# WatchDogAlarm_rev1_3.net
KiCad netlist of a schematic drawn in Altium Designer
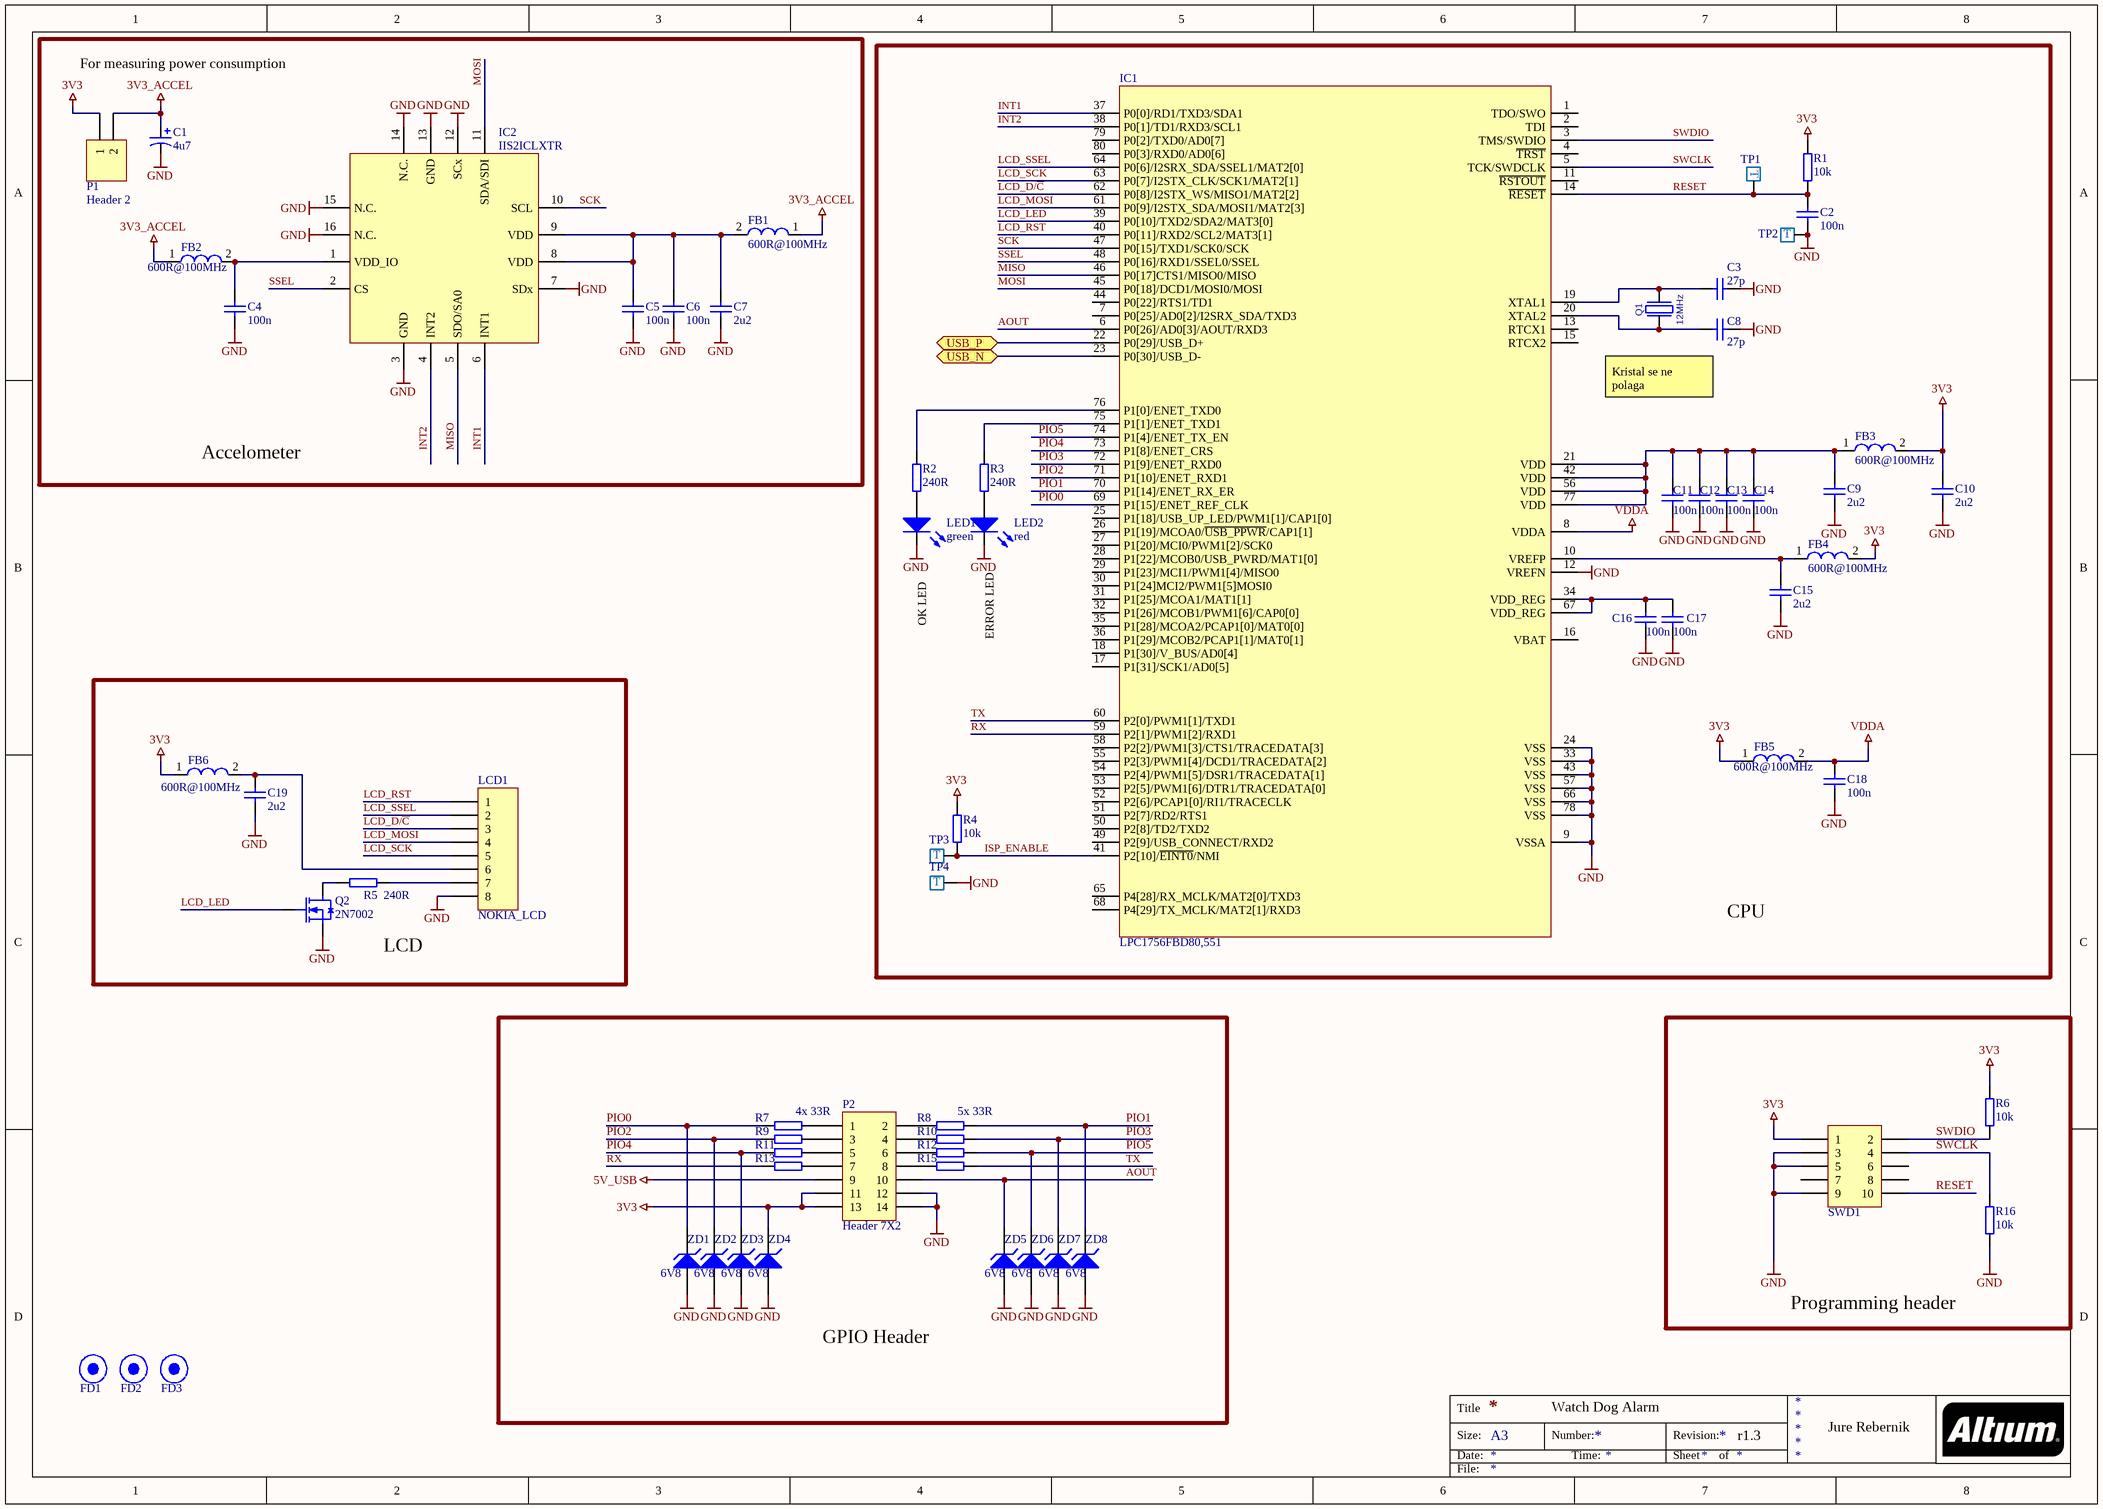
[diagram p0: WatchDogAlarm_rev1_3.SchDoc]

(export (version "E")
  (design (tool "Eeschema 10.0.6"))
  (components
    (comp (ref "C1")
      (value "4u7")
      (footprint "Tantalum 3216")
      (description "Generic polarized capacitor")
      (libsource (lib "WatchDogAlarm_rev1_3") (part "Capacitor - polarized"))
    )
    (comp (ref "C2")
      (value "100n")
      (footprint "SMD_C0603")
      (description "Capacitor")
      (libsource (lib "WatchDogAlarm_rev1_3") (part "CAP"))
    )
    (comp (ref "C3")
      (value "27p")
      (footprint "SMD_C0603")
      (description "Capacitor")
      (libsource (lib "WatchDogAlarm_rev1_3") (part "CAP"))
    )
    (comp (ref "C4")
      (value "100n")
      (footprint "SMD_C0603")
      (description "Capacitor")
      (libsource (lib "WatchDogAlarm_rev1_3") (part "CAP"))
    )
    (comp (ref "C5")
      (value "100n")
      (footprint "SMD_C0603")
      (description "Capacitor")
      (libsource (lib "WatchDogAlarm_rev1_3") (part "CAP"))
    )
    (comp (ref "C6")
      (value "100n")
      (footprint "SMD_C0603")
      (description "Capacitor")
      (libsource (lib "WatchDogAlarm_rev1_3") (part "CAP"))
    )
    (comp (ref "C7")
      (value "2u2")
      (footprint "SMD_C0805")
      (description "Capacitor")
      (libsource (lib "WatchDogAlarm_rev1_3") (part "CAP"))
    )
    (comp (ref "C8")
      (value "27p")
      (footprint "SMD_C0603")
      (description "Capacitor")
      (libsource (lib "WatchDogAlarm_rev1_3") (part "CAP"))
    )
    (comp (ref "C9")
      (value "2u2")
      (footprint "SMD_C0805")
      (description "Capacitor")
      (libsource (lib "WatchDogAlarm_rev1_3") (part "CAP"))
    )
    (comp (ref "C10")
      (value "2u2")
      (footprint "SMD_C0805")
      (description "Capacitor")
      (libsource (lib "WatchDogAlarm_rev1_3") (part "CAP"))
    )
    (comp (ref "C11")
      (value "100n")
      (footprint "SMD_C0603")
      (description "Capacitor")
      (libsource (lib "WatchDogAlarm_rev1_3") (part "CAP"))
    )
    (comp (ref "C12")
      (value "100n")
      (footprint "SMD_C0603")
      (description "Capacitor")
      (libsource (lib "WatchDogAlarm_rev1_3") (part "CAP"))
    )
    (comp (ref "C13")
      (value "100n")
      (footprint "SMD_C0603")
      (description "Capacitor")
      (libsource (lib "WatchDogAlarm_rev1_3") (part "CAP"))
    )
    (comp (ref "C14")
      (value "100n")
      (footprint "SMD_C0603")
      (description "Capacitor")
      (libsource (lib "WatchDogAlarm_rev1_3") (part "CAP"))
    )
    (comp (ref "C15")
      (value "2u2")
      (footprint "SMD_C0805")
      (description "Capacitor")
      (libsource (lib "WatchDogAlarm_rev1_3") (part "CAP"))
    )
    (comp (ref "C16")
      (value "100n")
      (footprint "SMD_C0603")
      (description "Capacitor")
      (libsource (lib "WatchDogAlarm_rev1_3") (part "CAP"))
    )
    (comp (ref "C17")
      (value "100n")
      (footprint "SMD_C0603")
      (description "Capacitor")
      (libsource (lib "WatchDogAlarm_rev1_3") (part "CAP"))
    )
    (comp (ref "C18")
      (value "100n")
      (footprint "SMD_C0603")
      (description "Capacitor")
      (libsource (lib "WatchDogAlarm_rev1_3") (part "CAP"))
    )
    (comp (ref "C19")
      (value "2u2")
      (footprint "SMD_C0805")
      (description "Capacitor")
      (libsource (lib "WatchDogAlarm_rev1_3") (part "CAP"))
    )
    (comp (ref "FB1")
      (value "600R@100MHz")
      (footprint "SMD_R0603")
      (description "Ferrite bead")
      (libsource (lib "") (part "FB_1"))
    )
    (comp (ref "FB2")
      (value "600R@100MHz")
      (footprint "SMD_R0603")
      (description "Ferrite bead")
      (libsource (lib "WatchDogAlarm_rev1_3") (part "FB"))
    )
    (comp (ref "FB3")
      (value "600R@100MHz")
      (footprint "SMD_R0603")
      (description "Ferrite bead")
      (libsource (lib "WatchDogAlarm_rev1_3") (part "FB"))
    )
    (comp (ref "FB4")
      (value "600R@100MHz")
      (footprint "SMD_R0603")
      (description "Ferrite bead")
      (libsource (lib "WatchDogAlarm_rev1_3") (part "FB"))
    )
    (comp (ref "FB5")
      (value "600R@100MHz")
      (footprint "SMD_R0603")
      (description "Ferrite bead")
      (libsource (lib "WatchDogAlarm_rev1_3") (part "FB"))
    )
    (comp (ref "FB6")
      (value "600R@100MHz")
      (footprint "SMD_R0603")
      (description "Ferrite bead")
      (libsource (lib "WatchDogAlarm_rev1_3") (part "FB"))
    )
    (comp (ref "FD1")
      (value "Fiducial 1mm")
      (footprint "FID1")
      (libsource (lib "WatchDogAlarm_rev1_3") (part "FIDUCIAL"))
    )
    (comp (ref "FD2")
      (value "Fiducial 1mm")
      (footprint "FID1")
      (libsource (lib "WatchDogAlarm_rev1_3") (part "FIDUCIAL"))
    )
    (comp (ref "FD3")
      (value "Fiducial 1mm")
      (footprint "FID1")
      (libsource (lib "WatchDogAlarm_rev1_3") (part "FIDUCIAL"))
    )
    (comp (ref "IC1")
      (value "LPC1756FBD80,551")
      (footprint "LQFP80")
      (description "LPC1756FBD80")
      (fields (field (name "MANUFACTURER") "NXP"))
      (libsource (lib "WatchDogAlarm_rev1_3") (part "LPC1756FBD80"))
    )
    (comp (ref "IC2")
      (value "IIS2ICLXTR")
      (footprint "LGA-16L")
      (fields (field (name "MANUFACTURER") "STM"))
      (libsource (lib "WatchDogAlarm_SchLib") (part "IIS2ICLXTR"))
    )
    (comp (ref "LCD1")
      (value "NOKIA_LCD")
      (footprint "NOKIA_LCD")
      (libsource (lib "WatchDogAlarm_rev1_3") (part "NOKIA_LCD"))
    )
    (comp (ref "LED1") (value "green") (footprint "SMD_LD0603") (libsource (lib "Atlan") (part "LED")))
    (comp (ref "LED2") (value "red") (footprint "SMD_LD0603") (libsource (lib "Atlan") (part "LED")))
    (comp (ref "P1")
      (value "Header 2")
      (footprint "HDR1X2")
      (description "Header, 2-Pin")
      (fields (field (name "PUBLISHER") "Altium Limited"))
      (libsource (lib "Miscellaneous Connectors") (part "Header 2"))
    )
    (comp (ref "P2")
      (value "Header 7X2")
      (footprint "HDR2X7")
      (description "Header, 7-Pin, Dual row")
      (fields (field (name "PUBLISHER") "Altium Limited"))
      (libsource (lib "WatchDogAlarm_rev1_3") (part "Header 7X2"))
    )
    (comp (ref "Q1")
      (value "12MHz")
      (footprint "QABM3")
      (description "Crystal")
      (fields (field (name "PARTNUMBER") "ABM3-12.000MHZ-D2Y-T") (field (name "MANUFACTURER") "ABRACON"))
      (libsource (lib "WatchDogAlarm_rev1_3") (part "Crystal"))
    )
    (comp (ref "Q2")
      (value "2N7002")
      (footprint "SOT-23")
      (description "Power MOSFET, N Channel, 60 V, 300 mA, 2.8 ohm, SOT-23, Surface Mount")
      (fields (field (name "MANUFACTURER") "NXP"))
      (libsource (lib "WatchDogAlarm_rev1_3") (part "N-MOSFET"))
    )
    (comp (ref "R1")
      (value "10k")
      (footprint "SMD_R0603")
      (libsource (lib "WatchDogAlarm_rev1_3") (part "RESISTOR"))
    )
    (comp (ref "R2")
      (value "240R")
      (footprint "SMD_R0603")
      (libsource (lib "WatchDogAlarm_rev1_3") (part "RESISTOR"))
    )
    (comp (ref "R3")
      (value "240R")
      (footprint "SMD_R0603")
      (libsource (lib "WatchDogAlarm_rev1_3") (part "RESISTOR"))
    )
    (comp (ref "R4")
      (value "10k")
      (footprint "SMD_R0603")
      (libsource (lib "WatchDogAlarm_rev1_3") (part "RESISTOR"))
    )
    (comp (ref "R5")
      (value "240R")
      (footprint "SMD_R0603")
      (libsource (lib "WatchDogAlarm_rev1_3") (part "RESISTOR"))
    )
    (comp (ref "R6")
      (value "10k")
      (footprint "SMD_R0603")
      (libsource (lib "WatchDogAlarm_rev1_3") (part "RESISTOR"))
    )
    (comp (ref "R7")
      (value "33R")
      (footprint "SMD_R0603")
      (libsource (lib "WatchDogAlarm_rev1_3") (part "RESISTOR"))
    )
    (comp (ref "R8")
      (value "33R")
      (footprint "SMD_R0603")
      (libsource (lib "WatchDogAlarm_rev1_3") (part "RESISTOR"))
    )
    (comp (ref "R9")
      (value "33R")
      (footprint "SMD_R0603")
      (libsource (lib "WatchDogAlarm_rev1_3") (part "RESISTOR"))
    )
    (comp (ref "R10")
      (value "33R")
      (footprint "SMD_R0603")
      (libsource (lib "WatchDogAlarm_rev1_3") (part "RESISTOR"))
    )
    (comp (ref "R11")
      (value "33R")
      (footprint "SMD_R0603")
      (libsource (lib "WatchDogAlarm_rev1_3") (part "RESISTOR"))
    )
    (comp (ref "R12")
      (value "33R")
      (footprint "SMD_R0603")
      (libsource (lib "WatchDogAlarm_rev1_3") (part "RESISTOR"))
    )
    (comp (ref "R13")
      (value "33R")
      (footprint "SMD_R0603")
      (libsource (lib "WatchDogAlarm_rev1_3") (part "RESISTOR"))
    )
    (comp (ref "R15")
      (value "33R")
      (footprint "SMD_R0603")
      (libsource (lib "WatchDogAlarm_rev1_3") (part "RESISTOR"))
    )
    (comp (ref "R16")
      (value "10k")
      (footprint "SMD_R0603")
      (libsource (lib "WatchDogAlarm_rev1_3") (part "RESISTOR"))
    )
    (comp (ref "SWD1")
      (value "Header 5x2")
      (footprint "2x5_SWD_CON")
      (description "Header, 5-Pin, Dual row")
      (fields (field (name "MANUFACTURER") "HARWIN") (field (name "PARTNUMBER") "M50-3500542"))
      (libsource (lib "WatchDogAlarm_rev1_3") (part "Header 5X2"))
    )
    (comp (ref "TP1")
      (value "TEST_PAD_1.5mm")
      (footprint "TEST_PAD_1.5mm")
      (libsource (lib "Atlan") (part "TEST_PAD"))
    )
    (comp (ref "TP2")
      (value "TEST_PAD_1.5mm")
      (footprint "TEST_PAD_1.5mm")
      (libsource (lib "Atlan") (part "TEST_PAD"))
    )
    (comp (ref "TP3")
      (value "TEST_PAD_1.5mm")
      (footprint "TEST_PAD_1.5mm")
      (libsource (lib "Atlan") (part "TEST_PAD"))
    )
    (comp (ref "TP4")
      (value "TEST_PAD_1.5mm")
      (footprint "TEST_PAD_1.5mm")
      (libsource (lib "Atlan") (part "TEST_PAD"))
    )
    (comp (ref "ZD1")
      (value "6V8")
      (footprint "SOT-23")
      (description "Zener Diode")
      (fields (field (name "MANUFACTURER") "ON Semiconductor") (field (name "PARTNUMBER") "BZX84C6V8LT1G"))
      (libsource (lib "WatchDogAlarm_rev1_3") (part "ZenerDiode"))
    )
    (comp (ref "ZD2")
      (value "6V8")
      (footprint "SOT-23")
      (description "Zener Diode")
      (fields (field (name "MANUFACTURER") "ON Semiconductor") (field (name "PARTNUMBER") "BZX84C6V8LT1G"))
      (libsource (lib "WatchDogAlarm_rev1_3") (part "ZenerDiode"))
    )
    (comp (ref "ZD3")
      (value "6V8")
      (footprint "SOT-23")
      (description "Zener Diode")
      (fields (field (name "MANUFACTURER") "ON Semiconductor") (field (name "PARTNUMBER") "BZX84C6V8LT1G"))
      (libsource (lib "WatchDogAlarm_rev1_3") (part "ZenerDiode"))
    )
    (comp (ref "ZD4")
      (value "6V8")
      (footprint "SOT-23")
      (description "Zener Diode")
      (fields (field (name "MANUFACTURER") "ON Semiconductor") (field (name "PARTNUMBER") "BZX84C6V8LT1G"))
      (libsource (lib "WatchDogAlarm_rev1_3") (part "ZenerDiode"))
    )
    (comp (ref "ZD5")
      (value "6V8")
      (footprint "SOT-23")
      (description "Zener Diode")
      (fields (field (name "MANUFACTURER") "ON Semiconductor") (field (name "PARTNUMBER") "BZX84C6V8LT1G"))
      (libsource (lib "WatchDogAlarm_rev1_3") (part "ZenerDiode"))
    )
    (comp (ref "ZD6")
      (value "6V8")
      (footprint "SOT-23")
      (description "Zener Diode")
      (fields (field (name "MANUFACTURER") "ON Semiconductor") (field (name "PARTNUMBER") "BZX84C6V8LT1G"))
      (libsource (lib "WatchDogAlarm_rev1_3") (part "ZenerDiode"))
    )
    (comp (ref "ZD7")
      (value "6V8")
      (footprint "SOT-23")
      (description "Zener Diode")
      (fields (field (name "MANUFACTURER") "ON Semiconductor") (field (name "PARTNUMBER") "BZX84C6V8LT1G"))
      (libsource (lib "WatchDogAlarm_rev1_3") (part "ZenerDiode"))
    )
    (comp (ref "ZD8")
      (value "6V8")
      (footprint "SOT-23")
      (description "Zener Diode")
      (fields (field (name "MANUFACTURER") "ON Semiconductor") (field (name "PARTNUMBER") "BZX84C6V8LT1G"))
      (libsource (lib "WatchDogAlarm_rev1_3") (part "ZenerDiode"))
    )
  )
  (nets
    (net (code "1") (name "/AOUT") (class "Default")
      (node (ref "IC1") (pin "6") (pinfunction "P0[26]/AD0[3]/AOUT/RXD3_6") (pintype "passive"))
      (node (ref "P2") (pin "10") (pinfunction "10_10") (pintype "passive"))
      (node (ref "ZD5") (pin "3") (pinfunction "K_3") (pintype "passive"))
    )
    (net (code "2") (name "/INT1") (class "Default")
      (node (ref "IC1") (pin "37") (pinfunction "P0[0]/RD1/TXD3/SDA1_37") (pintype "passive"))
      (node (ref "IC2") (pin "6") (pinfunction "INT1_6") (pintype "passive"))
    )
    (net (code "3") (name "/INT2") (class "Default")
      (node (ref "IC1") (pin "38") (pinfunction "P0[1]/TD1/RXD3/SCL1_38") (pintype "passive"))
      (node (ref "IC2") (pin "4") (pinfunction "INT2_4") (pintype "passive"))
    )
    (net (code "4") (name "/ISP_ENABLE") (class "Default")
      (node (ref "IC1") (pin "41") (pinfunction "P2[10]/~{EINT0}/NMI_41") (pintype "passive"))
      (node (ref "R4") (pin "1") (pintype "passive"))
      (node (ref "TP3") (pin "1") (pintype "passive"))
    )
    (net (code "5") (name "/LCD_D{slash}~{C}") (class "Default")
      (node (ref "IC1") (pin "62") (pinfunction "P0[8]/I2STX_WS/MISO1/MAT2[2]_62") (pintype "passive"))
      (node (ref "LCD1") (pin "3") (pinfunction "3_3") (pintype "passive"))
    )
    (net (code "6") (name "/LCD_LED") (class "Default")
      (node (ref "IC1") (pin "39") (pinfunction "P0[10]/TXD2/SDA2/MAT3[0]_39") (pintype "passive"))
      (node (ref "Q2") (pin "1") (pinfunction "G_1") (pintype "passive"))
    )
    (net (code "7") (name "/LCD_MOSI") (class "Default")
      (node (ref "IC1") (pin "61") (pinfunction "P0[9]/I2STX_SDA/MOSI1/MAT2[3]_61") (pintype "passive"))
      (node (ref "LCD1") (pin "4") (pinfunction "4_4") (pintype "passive"))
    )
    (net (code "8") (name "/LCD_RST") (class "Default")
      (node (ref "IC1") (pin "40") (pinfunction "P0[11]/RXD2/SCL2/MAT3[1]_40") (pintype "passive"))
      (node (ref "LCD1") (pin "1") (pinfunction "1_1") (pintype "passive"))
    )
    (net (code "9") (name "/LCD_SCK") (class "Default")
      (node (ref "IC1") (pin "63") (pinfunction "P0[7]/I2STX_CLK/SCK1/MAT2[1]_63") (pintype "passive"))
      (node (ref "LCD1") (pin "5") (pinfunction "5_5") (pintype "passive"))
    )
    (net (code "10") (name "/LCD_SSEL") (class "Default")
      (node (ref "IC1") (pin "64") (pinfunction "P0[6]/I2SRX_SDA/SSEL1/MAT2[0]_64") (pintype "passive"))
      (node (ref "LCD1") (pin "2") (pinfunction "2_2") (pintype "passive"))
    )
    (net (code "11") (name "/MISO") (class "Default")
      (node (ref "IC1") (pin "46") (pinfunction "P0[17]CTS1/MISO0/MISO_46") (pintype "passive"))
      (node (ref "IC2") (pin "5") (pinfunction "SDO/SA0_5") (pintype "passive"))
    )
    (net (code "12") (name "/MOSI") (class "Default")
      (node (ref "IC1") (pin "45") (pinfunction "P0[18]/DCD1/MOSI0/MOSI_45") (pintype "passive"))
      (node (ref "IC2") (pin "11") (pinfunction "SDA/SDI_11") (pintype "passive"))
    )
    (net (code "13") (name "/PIO0") (class "Default")
      (node (ref "IC1") (pin "69") (pinfunction "P1[15]/ENET_REF_CLK_69") (pintype "passive"))
      (node (ref "R7") (pin "2") (pintype "passive"))
      (node (ref "ZD1") (pin "3") (pinfunction "K_3") (pintype "passive"))
    )
    (net (code "14") (name "/PIO1") (class "Default")
      (node (ref "IC1") (pin "70") (pinfunction "P1[14]/ENET_RX_ER_70") (pintype "passive"))
      (node (ref "R8") (pin "1") (pintype "passive"))
      (node (ref "ZD8") (pin "3") (pinfunction "K_3") (pintype "passive"))
    )
    (net (code "15") (name "/PIO2") (class "Default")
      (node (ref "IC1") (pin "71") (pinfunction "P1[10]/ENET_RXD1_71") (pintype "passive"))
      (node (ref "R9") (pin "2") (pintype "passive"))
      (node (ref "ZD2") (pin "3") (pinfunction "K_3") (pintype "passive"))
    )
    (net (code "16") (name "/PIO3") (class "Default")
      (node (ref "IC1") (pin "72") (pinfunction "P1[9]/ENET_RXD0_72") (pintype "passive"))
      (node (ref "R10") (pin "1") (pintype "passive"))
      (node (ref "ZD7") (pin "3") (pinfunction "K_3") (pintype "passive"))
    )
    (net (code "17") (name "/PIO4") (class "Default")
      (node (ref "IC1") (pin "73") (pinfunction "P1[8]/ENET_CRS_73") (pintype "passive"))
      (node (ref "R11") (pin "2") (pintype "passive"))
      (node (ref "ZD3") (pin "3") (pinfunction "K_3") (pintype "passive"))
    )
    (net (code "18") (name "/PIO5") (class "Default")
      (node (ref "IC1") (pin "74") (pinfunction "P1[4]/ENET_TX_EN_74") (pintype "passive"))
      (node (ref "R12") (pin "1") (pintype "passive"))
      (node (ref "ZD6") (pin "3") (pinfunction "K_3") (pintype "passive"))
    )
    (net (code "19") (name "/RESET") (class "Default")
      (node (ref "C2") (pin "2") (pinfunction "2_2") (pintype "passive"))
      (node (ref "IC1") (pin "14") (pinfunction "~{RESET}_14") (pintype "passive"))
      (node (ref "R1") (pin "1") (pintype "passive"))
      (node (ref "SWD1") (pin "10") (pinfunction "10_10") (pintype "passive"))
      (node (ref "TP1") (pin "1") (pintype "passive"))
    )
    (net (code "20") (name "/RX") (class "Default")
      (node (ref "IC1") (pin "59") (pinfunction "P2[1]/PWM1[2]/RXD1_59") (pintype "passive"))
      (node (ref "R13") (pin "2") (pintype "passive"))
    )
    (net (code "21") (name "/SCK") (class "Default")
      (node (ref "IC1") (pin "47") (pinfunction "P0[15]/TXD1/SCK0/SCK_47") (pintype "passive"))
      (node (ref "IC2") (pin "10") (pinfunction "SCL_10") (pintype "passive"))
    )
    (net (code "22") (name "/SSEL") (class "Default")
      (node (ref "IC1") (pin "48") (pinfunction "P0[16]/RXD1/SSEL0/SSEL_48") (pintype "passive"))
      (node (ref "IC2") (pin "2") (pinfunction "CS_2") (pintype "passive"))
    )
    (net (code "23") (name "/SWCLK") (class "Default")
      (node (ref "IC1") (pin "5") (pinfunction "TCK/SWDCLK_5") (pintype "passive"))
      (node (ref "R16") (pin "2") (pintype "passive"))
      (node (ref "SWD1") (pin "4") (pinfunction "4_4") (pintype "passive"))
    )
    (net (code "24") (name "/SWDIO") (class "Default")
      (node (ref "IC1") (pin "3") (pinfunction "TMS/SWDIO_3") (pintype "passive"))
      (node (ref "R6") (pin "1") (pintype "passive"))
      (node (ref "SWD1") (pin "2") (pinfunction "2_2") (pintype "passive"))
    )
    (net (code "25") (name "/TX") (class "Default")
      (node (ref "IC1") (pin "60") (pinfunction "P2[0]/PWM1[1]/TXD1_60") (pintype "passive"))
      (node (ref "R15") (pin "1") (pintype "passive"))
    )
    (net (code "26") (name "/USB_N") (class "Default")
      (node (ref "IC1") (pin "23") (pinfunction "P0[30]/USB_D-_23") (pintype "passive"))
    )
    (net (code "27") (name "/USB_P") (class "Default")
      (node (ref "IC1") (pin "22") (pinfunction "P0[29]/USB_D+_22") (pintype "passive"))
    )
    (net (code "28") (name "3V3") (class "Default")
      (node (ref "C10") (pin "2") (pinfunction "2_2") (pintype "passive"))
      (node (ref "FB3") (pin "2") (pinfunction "2_2") (pintype "passive"))
      (node (ref "FB4") (pin "2") (pinfunction "2_2") (pintype "passive"))
      (node (ref "FB5") (pin "1") (pinfunction "1_1") (pintype "passive"))
      (node (ref "FB6") (pin "1") (pinfunction "1_1") (pintype "passive"))
      (node (ref "P1") (pin "1") (pinfunction "1_1") (pintype "passive"))
      (node (ref "P2") (pin "11") (pinfunction "11_11") (pintype "passive"))
      (node (ref "P2") (pin "13") (pinfunction "13_13") (pintype "passive"))
      (node (ref "R1") (pin "2") (pintype "passive"))
      (node (ref "R4") (pin "2") (pintype "passive"))
      (node (ref "R6") (pin "2") (pintype "passive"))
      (node (ref "SWD1") (pin "1") (pinfunction "1_1") (pintype "passive"))
      (node (ref "ZD4") (pin "3") (pinfunction "K_3") (pintype "passive"))
    )
    (net (code "29") (name "3V3_ACCEL") (class "Default")
      (node (ref "C1") (pin "1") (pinfunction "1_1") (pintype "passive"))
      (node (ref "FB1") (pin "1") (pinfunction "1_1") (pintype "passive"))
      (node (ref "FB2") (pin "1") (pinfunction "1_1") (pintype "passive"))
      (node (ref "P1") (pin "2") (pinfunction "2_2") (pintype "passive"))
    )
    (net (code "30") (name "5V_USB") (class "Default")
      (node (ref "P2") (pin "9") (pinfunction "9_9") (pintype "passive"))
    )
    (net (code "31") (name "GND") (class "Default")
      (node (ref "C1") (pin "2") (pinfunction "2_2") (pintype "passive"))
      (node (ref "C10") (pin "1") (pinfunction "1_1") (pintype "passive"))
      (node (ref "C11") (pin "1") (pinfunction "1_1") (pintype "passive"))
      (node (ref "C12") (pin "1") (pinfunction "1_1") (pintype "passive"))
      (node (ref "C13") (pin "1") (pinfunction "1_1") (pintype "passive"))
      (node (ref "C14") (pin "1") (pinfunction "1_1") (pintype "passive"))
      (node (ref "C15") (pin "1") (pinfunction "1_1") (pintype "passive"))
      (node (ref "C16") (pin "1") (pinfunction "1_1") (pintype "passive"))
      (node (ref "C17") (pin "1") (pinfunction "1_1") (pintype "passive"))
      (node (ref "C18") (pin "2") (pinfunction "2_2") (pintype "passive"))
      (node (ref "C19") (pin "1") (pinfunction "1_1") (pintype "passive"))
      (node (ref "C2") (pin "1") (pinfunction "1_1") (pintype "passive"))
      (node (ref "C3") (pin "1") (pinfunction "1_1") (pintype "passive"))
      (node (ref "C4") (pin "1") (pinfunction "1_1") (pintype "passive"))
      (node (ref "C5") (pin "1") (pinfunction "1_1") (pintype "passive"))
      (node (ref "C6") (pin "1") (pinfunction "1_1") (pintype "passive"))
      (node (ref "C7") (pin "1") (pinfunction "1_1") (pintype "passive"))
      (node (ref "C8") (pin "1") (pinfunction "1_1") (pintype "passive"))
      (node (ref "C9") (pin "1") (pinfunction "1_1") (pintype "passive"))
      (node (ref "IC1") (pin "12") (pinfunction "VREFN_12") (pintype "passive"))
      (node (ref "IC1") (pin "24") (pinfunction "VSS_24") (pintype "passive"))
      (node (ref "IC1") (pin "33") (pinfunction "VSS_33") (pintype "passive"))
      (node (ref "IC1") (pin "43") (pinfunction "VSS_43") (pintype "passive"))
      (node (ref "IC1") (pin "57") (pinfunction "VSS_57") (pintype "passive"))
      (node (ref "IC1") (pin "66") (pinfunction "VSS_66") (pintype "passive"))
      (node (ref "IC1") (pin "78") (pinfunction "VSS_78") (pintype "passive"))
      (node (ref "IC1") (pin "9") (pinfunction "VSSA_9") (pintype "passive"))
      (node (ref "IC2") (pin "12") (pinfunction "SCx_12") (pintype "passive"))
      (node (ref "IC2") (pin "13") (pinfunction "GND_13") (pintype "passive"))
      (node (ref "IC2") (pin "14") (pinfunction "N.C._14") (pintype "passive"))
      (node (ref "IC2") (pin "15") (pinfunction "N.C._15") (pintype "passive"))
      (node (ref "IC2") (pin "16") (pinfunction "N.C._16") (pintype "passive"))
      (node (ref "IC2") (pin "3") (pinfunction "GND_3") (pintype "passive"))
      (node (ref "IC2") (pin "7") (pinfunction "SDx_7") (pintype "passive"))
      (node (ref "LCD1") (pin "8") (pinfunction "8_8") (pintype "passive"))
      (node (ref "LED1") (pin "1") (pinfunction "K_1") (pintype "passive"))
      (node (ref "LED2") (pin "1") (pinfunction "K_1") (pintype "passive"))
      (node (ref "P2") (pin "12") (pinfunction "12_12") (pintype "passive"))
      (node (ref "P2") (pin "14") (pinfunction "14_14") (pintype "passive"))
      (node (ref "Q2") (pin "2") (pinfunction "S_2") (pintype "passive"))
      (node (ref "R16") (pin "1") (pintype "passive"))
      (node (ref "SWD1") (pin "3") (pinfunction "3_3") (pintype "passive"))
      (node (ref "SWD1") (pin "5") (pinfunction "5_5") (pintype "passive"))
      (node (ref "SWD1") (pin "9") (pinfunction "9_9") (pintype "passive"))
      (node (ref "TP2") (pin "1") (pintype "passive"))
      (node (ref "TP4") (pin "1") (pintype "passive"))
      (node (ref "ZD1") (pin "1") (pinfunction "A_1") (pintype "passive"))
      (node (ref "ZD2") (pin "1") (pinfunction "A_1") (pintype "passive"))
      (node (ref "ZD3") (pin "1") (pinfunction "A_1") (pintype "passive"))
      (node (ref "ZD4") (pin "1") (pinfunction "A_1") (pintype "passive"))
      (node (ref "ZD5") (pin "1") (pinfunction "A_1") (pintype "passive"))
      (node (ref "ZD6") (pin "1") (pinfunction "A_1") (pintype "passive"))
      (node (ref "ZD7") (pin "1") (pinfunction "A_1") (pintype "passive"))
      (node (ref "ZD8") (pin "1") (pinfunction "A_1") (pintype "passive"))
    )
    (net (code "32") (name "Net-(C5-Pad2)") (class "Default")
      (node (ref "C5") (pin "2") (pinfunction "2_2") (pintype "passive"))
      (node (ref "C6") (pin "2") (pinfunction "2_2") (pintype "passive"))
      (node (ref "C7") (pin "2") (pinfunction "2_2") (pintype "passive"))
      (node (ref "FB1") (pin "2") (pinfunction "2_2") (pintype "passive"))
      (node (ref "IC2") (pin "8") (pinfunction "VDD_8") (pintype "passive"))
      (node (ref "IC2") (pin "9") (pinfunction "VDD_9") (pintype "passive"))
    )
    (net (code "33") (name "Net-(C11-Pad2)") (class "Default")
      (node (ref "C11") (pin "2") (pinfunction "2_2") (pintype "passive"))
      (node (ref "C12") (pin "2") (pinfunction "2_2") (pintype "passive"))
      (node (ref "C13") (pin "2") (pinfunction "2_2") (pintype "passive"))
      (node (ref "C14") (pin "2") (pinfunction "2_2") (pintype "passive"))
      (node (ref "C9") (pin "2") (pinfunction "2_2") (pintype "passive"))
      (node (ref "FB3") (pin "1") (pinfunction "1_1") (pintype "passive"))
      (node (ref "IC1") (pin "21") (pinfunction "VDD_21") (pintype "passive"))
      (node (ref "IC1") (pin "42") (pinfunction "VDD_42") (pintype "passive"))
      (node (ref "IC1") (pin "56") (pinfunction "VDD_56") (pintype "passive"))
      (node (ref "IC1") (pin "77") (pinfunction "VDD_77") (pintype "passive"))
    )
    (net (code "34") (name "Net-(C16-Pad2)") (class "Default")
      (node (ref "C16") (pin "2") (pinfunction "2_2") (pintype "passive"))
      (node (ref "C17") (pin "2") (pinfunction "2_2") (pintype "passive"))
      (node (ref "IC1") (pin "34") (pinfunction "VDD_REG_34") (pintype "passive"))
      (node (ref "IC1") (pin "67") (pinfunction "VDD_REG_67") (pintype "passive"))
    )
    (net (code "35") (name "Net-(C19-Pad2)") (class "Default")
      (node (ref "C19") (pin "2") (pinfunction "2_2") (pintype "passive"))
      (node (ref "FB6") (pin "2") (pinfunction "2_2") (pintype "passive"))
      (node (ref "LCD1") (pin "6") (pinfunction "6_6") (pintype "passive"))
    )
    (net (code "36") (name "Net-(IC1-P1[0]{slash}ENET_TXD0)") (class "Default")
      (node (ref "IC1") (pin "76") (pinfunction "P1[0]/ENET_TXD0_76") (pintype "passive"))
      (node (ref "R2") (pin "2") (pintype "passive"))
    )
    (net (code "37") (name "Net-(IC1-P1[1]{slash}ENET_TXD1)") (class "Default")
      (node (ref "IC1") (pin "75") (pinfunction "P1[1]/ENET_TXD1_75") (pintype "passive"))
      (node (ref "R3") (pin "2") (pintype "passive"))
    )
    (net (code "38") (name "Net-(IC1-VREFP)") (class "Default")
      (node (ref "C15") (pin "2") (pinfunction "2_2") (pintype "passive"))
      (node (ref "FB4") (pin "1") (pinfunction "1_1") (pintype "passive"))
      (node (ref "IC1") (pin "10") (pinfunction "VREFP_10") (pintype "passive"))
    )
    (net (code "39") (name "Net-(IC1-XTAL1)") (class "Default")
      (node (ref "C3") (pin "2") (pinfunction "2_2") (pintype "passive"))
      (node (ref "IC1") (pin "19") (pinfunction "XTAL1_19") (pintype "passive"))
      (node (ref "Q1") (pin "1") (pinfunction "1_1") (pintype "passive"))
    )
    (net (code "40") (name "Net-(IC1-XTAL2)") (class "Default")
      (node (ref "C8") (pin "2") (pinfunction "2_2") (pintype "passive"))
      (node (ref "IC1") (pin "20") (pinfunction "XTAL2_20") (pintype "passive"))
      (node (ref "Q1") (pin "2") (pinfunction "2_2") (pintype "passive"))
    )
    (net (code "41") (name "Net-(IC2-VDD_IO)") (class "Default")
      (node (ref "C4") (pin "2") (pinfunction "2_2") (pintype "passive"))
      (node (ref "FB2") (pin "2") (pinfunction "2_2") (pintype "passive"))
      (node (ref "IC2") (pin "1") (pinfunction "VDD_IO_1") (pintype "passive"))
    )
    (net (code "42") (name "Net-(LCD1-Pad7)") (class "Default")
      (node (ref "LCD1") (pin "7") (pinfunction "7_7") (pintype "passive"))
      (node (ref "R5") (pin "1") (pintype "passive"))
    )
    (net (code "43") (name "Net-(LED1-A)") (class "Default")
      (node (ref "LED1") (pin "2") (pinfunction "A_2") (pintype "passive"))
      (node (ref "R2") (pin "1") (pintype "passive"))
    )
    (net (code "44") (name "Net-(LED2-A)") (class "Default")
      (node (ref "LED2") (pin "2") (pinfunction "A_2") (pintype "passive"))
      (node (ref "R3") (pin "1") (pintype "passive"))
    )
    (net (code "45") (name "Net-(P2-Pad1)") (class "Default")
      (node (ref "P2") (pin "1") (pinfunction "1_1") (pintype "passive"))
      (node (ref "R7") (pin "1") (pintype "passive"))
    )
    (net (code "46") (name "Net-(P2-Pad2)") (class "Default")
      (node (ref "P2") (pin "2") (pinfunction "2_2") (pintype "passive"))
      (node (ref "R8") (pin "2") (pintype "passive"))
    )
    (net (code "47") (name "Net-(P2-Pad3)") (class "Default")
      (node (ref "P2") (pin "3") (pinfunction "3_3") (pintype "passive"))
      (node (ref "R9") (pin "1") (pintype "passive"))
    )
    (net (code "48") (name "Net-(P2-Pad4)") (class "Default")
      (node (ref "P2") (pin "4") (pinfunction "4_4") (pintype "passive"))
      (node (ref "R10") (pin "2") (pintype "passive"))
    )
    (net (code "49") (name "Net-(P2-Pad5)") (class "Default")
      (node (ref "P2") (pin "5") (pinfunction "5_5") (pintype "passive"))
      (node (ref "R11") (pin "1") (pintype "passive"))
    )
    (net (code "50") (name "Net-(P2-Pad6)") (class "Default")
      (node (ref "P2") (pin "6") (pinfunction "6_6") (pintype "passive"))
      (node (ref "R12") (pin "2") (pintype "passive"))
    )
    (net (code "51") (name "Net-(P2-Pad7)") (class "Default")
      (node (ref "P2") (pin "7") (pinfunction "7_7") (pintype "passive"))
      (node (ref "R13") (pin "1") (pintype "passive"))
    )
    (net (code "52") (name "Net-(P2-Pad8)") (class "Default")
      (node (ref "P2") (pin "8") (pinfunction "8_8") (pintype "passive"))
      (node (ref "R15") (pin "2") (pintype "passive"))
    )
    (net (code "53") (name "Net-(Q2-D)") (class "Default")
      (node (ref "Q2") (pin "3") (pinfunction "D_3") (pintype "passive"))
      (node (ref "R5") (pin "2") (pintype "passive"))
    )
    (net (code "54") (name "VDDA") (class "Default")
      (node (ref "C18") (pin "1") (pinfunction "1_1") (pintype "passive"))
      (node (ref "FB5") (pin "2") (pinfunction "2_2") (pintype "passive"))
      (node (ref "IC1") (pin "8") (pinfunction "VDDA_8") (pintype "passive"))
    )
    (net (code "55") (name "unconnected-(IC1-P0[2]{slash}TXD0{slash}AD0[7]-Pad79)") (class "Default")
      (node (ref "IC1") (pin "79") (pinfunction "P0[2]/TXD0/AD0[7]_79") (pintype "passive"))
    )
    (net (code "56") (name "unconnected-(IC1-P0[3]{slash}RXD0{slash}AD0[6]-Pad80)") (class "Default")
      (node (ref "IC1") (pin "80") (pinfunction "P0[3]/RXD0/AD0[6]_80") (pintype "passive"))
    )
    (net (code "57") (name "unconnected-(IC1-P0[22]{slash}RTS1{slash}TD1-Pad44)") (class "Default")
      (node (ref "IC1") (pin "44") (pinfunction "P0[22]/RTS1/TD1_44") (pintype "passive"))
    )
    (net (code "58") (name "unconnected-(IC1-P0[25]{slash}AD0[2]{slash}I2SRX_SDA{slash}TXD3-Pad7)") (class "Default")
      (node (ref "IC1") (pin "7") (pinfunction "P0[25]/AD0[2]/I2SRX_SDA/TXD3_7") (pintype "passive"))
    )
    (net (code "59") (name "unconnected-(IC1-P1[18]{slash}USB_UP_LED{slash}PWM1[1]{slash}CAP1[0]-Pad25)") (class "Default")
      (node (ref "IC1") (pin "25") (pinfunction "P1[18]/USB_UP_LED/PWM1[1]/CAP1[0]_25") (pintype "passive"))
    )
    (net (code "60") (name "unconnected-(IC1-P1[19]{slash}MCOA0{slash}~{USB_PPWR}{slash}CAP1[1]-Pad26)") (class "Default")
      (node (ref "IC1") (pin "26") (pinfunction "P1[19]/MCOA0/~{USB_PPWR}/CAP1[1]_26") (pintype "passive"))
    )
    (net (code "61") (name "unconnected-(IC1-P1[20]{slash}MCI0{slash}PWM1[2]{slash}SCK0-Pad27)") (class "Default")
      (node (ref "IC1") (pin "27") (pinfunction "P1[20]/MCI0/PWM1[2]/SCK0_27") (pintype "passive"))
    )
    (net (code "62") (name "unconnected-(IC1-P1[22]{slash}MCOB0{slash}USB_PWRD{slash}MAT1[0]-Pad28)") (class "Default")
      (node (ref "IC1") (pin "28") (pinfunction "P1[22]/MCOB0/USB_PWRD/MAT1[0]_28") (pintype "passive"))
    )
    (net (code "63") (name "unconnected-(IC1-P1[23]{slash}MCI1{slash}PWM1[4]{slash}MISO0-Pad29)") (class "Default")
      (node (ref "IC1") (pin "29") (pinfunction "P1[23]/MCI1/PWM1[4]/MISO0_29") (pintype "passive"))
    )
    (net (code "64") (name "unconnected-(IC1-P1[24]MCI2{slash}PWM1[5]MOSI0-Pad30)") (class "Default")
      (node (ref "IC1") (pin "30") (pinfunction "P1[24]MCI2/PWM1[5]MOSI0_30") (pintype "passive"))
    )
    (net (code "65") (name "unconnected-(IC1-P1[25]{slash}MCOA1{slash}MAT1[1]-Pad31)") (class "Default")
      (node (ref "IC1") (pin "31") (pinfunction "P1[25]/MCOA1/MAT1[1]_31") (pintype "passive"))
    )
    (net (code "66") (name "unconnected-(IC1-P1[26]{slash}MCOB1{slash}PWM1[6]{slash}CAP0[0]-Pad32)") (class "Default")
      (node (ref "IC1") (pin "32") (pinfunction "P1[26]/MCOB1/PWM1[6]/CAP0[0]_32") (pintype "passive"))
    )
    (net (code "67") (name "unconnected-(IC1-P1[28]{slash}MCOA2{slash}PCAP1[0]{slash}MAT0[0]-Pad35)") (class "Default")
      (node (ref "IC1") (pin "35") (pinfunction "P1[28]/MCOA2/PCAP1[0]/MAT0[0]_35") (pintype "passive"))
    )
    (net (code "68") (name "unconnected-(IC1-P1[29]{slash}MCOB2{slash}PCAP1[1]{slash}MAT0[1]-Pad36)") (class "Default")
      (node (ref "IC1") (pin "36") (pinfunction "P1[29]/MCOB2/PCAP1[1]/MAT0[1]_36") (pintype "passive"))
    )
    (net (code "69") (name "unconnected-(IC1-P1[30]{slash}V_BUS{slash}AD0[4]-Pad18)") (class "Default")
      (node (ref "IC1") (pin "18") (pinfunction "P1[30]/V_BUS/AD0[4]_18") (pintype "passive"))
    )
    (net (code "70") (name "unconnected-(IC1-P1[31]{slash}SCK1{slash}AD0[5]-Pad17)") (class "Default")
      (node (ref "IC1") (pin "17") (pinfunction "P1[31]/SCK1/AD0[5]_17") (pintype "passive"))
    )
    (net (code "71") (name "unconnected-(IC1-P2[2]{slash}PWM1[3]{slash}CTS1{slash}TRACEDATA[3]-Pad58)") (class "Default")
      (node (ref "IC1") (pin "58") (pinfunction "P2[2]/PWM1[3]/CTS1/TRACEDATA[3]_58") (pintype "passive"))
    )
    (net (code "72") (name "unconnected-(IC1-P2[3]{slash}PWM1[4]{slash}DCD1{slash}TRACEDATA[2]-Pad55)") (class "Default")
      (node (ref "IC1") (pin "55") (pinfunction "P2[3]/PWM1[4]/DCD1/TRACEDATA[2]_55") (pintype "passive"))
    )
    (net (code "73") (name "unconnected-(IC1-P2[4]{slash}PWM1[5]{slash}DSR1{slash}TRACEDATA[1]-Pad54)") (class "Default")
      (node (ref "IC1") (pin "54") (pinfunction "P2[4]/PWM1[5]/DSR1/TRACEDATA[1]_54") (pintype "passive"))
    )
    (net (code "74") (name "unconnected-(IC1-P2[5]{slash}PWM1[6]{slash}DTR1{slash}TRACEDATA[0]-Pad53)") (class "Default")
      (node (ref "IC1") (pin "53") (pinfunction "P2[5]/PWM1[6]/DTR1/TRACEDATA[0]_53") (pintype "passive"))
    )
    (net (code "75") (name "unconnected-(IC1-P2[6]{slash}PCAP1[0]{slash}RI1{slash}TRACECLK-Pad52)") (class "Default")
      (node (ref "IC1") (pin "52") (pinfunction "P2[6]/PCAP1[0]/RI1/TRACECLK_52") (pintype "passive"))
    )
    (net (code "76") (name "unconnected-(IC1-P2[7]{slash}RD2{slash}RTS1-Pad51)") (class "Default")
      (node (ref "IC1") (pin "51") (pinfunction "P2[7]/RD2/RTS1_51") (pintype "passive"))
    )
    (net (code "77") (name "unconnected-(IC1-P2[8]{slash}TD2{slash}TXD2-Pad50)") (class "Default")
      (node (ref "IC1") (pin "50") (pinfunction "P2[8]/TD2/TXD2_50") (pintype "passive"))
    )
    (net (code "78") (name "unconnected-(IC1-P2[9]{slash}USB_CONNECT{slash}RXD2-Pad49)") (class "Default")
      (node (ref "IC1") (pin "49") (pinfunction "P2[9]/USB_CONNECT/RXD2_49") (pintype "passive"))
    )
    (net (code "79") (name "unconnected-(IC1-P4[28]{slash}RX_MCLK{slash}MAT2[0]{slash}TXD3-Pad65)") (class "Default")
      (node (ref "IC1") (pin "65") (pinfunction "P4[28]/RX_MCLK/MAT2[0]/TXD3_65") (pintype "passive"))
    )
    (net (code "80") (name "unconnected-(IC1-P4[29]{slash}TX_MCLK{slash}MAT2[1]{slash}RXD3-Pad68)") (class "Default")
      (node (ref "IC1") (pin "68") (pinfunction "P4[29]/TX_MCLK/MAT2[1]/RXD3_68") (pintype "passive"))
    )
    (net (code "81") (name "unconnected-(IC1-RTCX1-Pad13)") (class "Default")
      (node (ref "IC1") (pin "13") (pinfunction "RTCX1_13") (pintype "passive"))
    )
    (net (code "82") (name "unconnected-(IC1-RTCX2-Pad15)") (class "Default")
      (node (ref "IC1") (pin "15") (pinfunction "RTCX2_15") (pintype "passive"))
    )
    (net (code "83") (name "unconnected-(IC1-TDI-Pad2)") (class "Default")
      (node (ref "IC1") (pin "2") (pinfunction "TDI_2") (pintype "passive"))
    )
    (net (code "84") (name "unconnected-(IC1-TDO{slash}SWO-Pad1)") (class "Default")
      (node (ref "IC1") (pin "1") (pinfunction "TDO/SWO_1") (pintype "passive"))
    )
    (net (code "85") (name "unconnected-(IC1-VBAT-Pad16)") (class "Default")
      (node (ref "IC1") (pin "16") (pinfunction "VBAT_16") (pintype "passive"))
    )
    (net (code "86") (name "unconnected-(IC1-~{RSTOUT}-Pad11)") (class "Default")
      (node (ref "IC1") (pin "11") (pinfunction "~{RSTOUT}_11") (pintype "passive"))
    )
    (net (code "87") (name "unconnected-(IC1-~{TRST}-Pad4)") (class "Default")
      (node (ref "IC1") (pin "4") (pinfunction "~{TRST}_4") (pintype "passive"))
    )
    (net (code "88") (name "unconnected-(SWD1-Pad6)") (class "Default")
      (node (ref "SWD1") (pin "6") (pinfunction "6_6") (pintype "passive"))
    )
    (net (code "89") (name "unconnected-(SWD1-Pad7)") (class "Default")
      (node (ref "SWD1") (pin "7") (pinfunction "7_7") (pintype "passive"))
    )
    (net (code "90") (name "unconnected-(SWD1-Pad8)") (class "Default")
      (node (ref "SWD1") (pin "8") (pinfunction "8_8") (pintype "passive"))
    )
  )
)
